# comparator.net
KiCad netlist of a schematic drawn in EAGLE
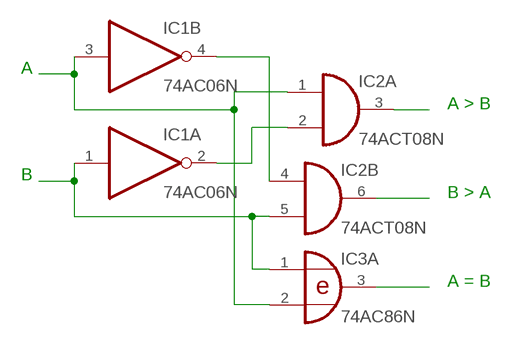
[diagram p0: schematic, sheet 1]

(export (version "E")
  (design (tool "Eeschema 10.0.6"))
  (components
    (comp (ref "IC1")
      (value "74AC06N")
      (footprint "eagle-import:DIL14")
      (libsource (lib "eagle-import") (part "7406NAC"))
    )
    (comp (ref "IC2")
      (value "74ACT08N")
      (footprint "eagle-import:DIL14")
      (libsource (lib "eagle-import") (part "7408NACT"))
    )
    (comp (ref "IC3")
      (value "74AC86N")
      (footprint "eagle-import:DIL14")
      (libsource (lib "eagle-import") (part "7486NAC"))
    )
  )
  (nets
    (net (code "1") (name "Net-(IC1A-I)") (class "Default")
      (node (ref "IC1") (pin "1") (pinfunction "I_1") (pintype "input"))
      (node (ref "IC2") (pin "5") (pinfunction "I1_5") (pintype "input"))
      (node (ref "IC3") (pin "1") (pinfunction "I0_1") (pintype "input"))
    )
    (net (code "2") (name "Net-(IC1A-O)") (class "Default")
      (node (ref "IC1") (pin "2") (pinfunction "O_2") (pintype "open_collector"))
      (node (ref "IC2") (pin "2") (pinfunction "I1_2") (pintype "input"))
    )
    (net (code "3") (name "Net-(IC1B-I)") (class "Default")
      (node (ref "IC1") (pin "3") (pinfunction "I_3") (pintype "input"))
      (node (ref "IC2") (pin "1") (pinfunction "I0_1") (pintype "input"))
      (node (ref "IC3") (pin "2") (pinfunction "I1_2") (pintype "input"))
    )
    (net (code "4") (name "Net-(IC1B-O)") (class "Default")
      (node (ref "IC1") (pin "4") (pinfunction "O_4") (pintype "open_collector"))
      (node (ref "IC2") (pin "4") (pinfunction "I0_4") (pintype "input"))
    )
    (net (code "5") (name "unconnected-(IC2A-O-Pad3)") (class "Default")
      (node (ref "IC2") (pin "3") (pinfunction "O_3") (pintype "output"))
    )
    (net (code "6") (name "unconnected-(IC2B-O-Pad6)") (class "Default")
      (node (ref "IC2") (pin "6") (pinfunction "O_6") (pintype "output"))
    )
    (net (code "7") (name "unconnected-(IC3A-O-Pad3)") (class "Default")
      (node (ref "IC3") (pin "3") (pinfunction "O_3") (pintype "output"))
    )
  )
)
